# cryobondr-qbit2-aqc.net
KiCad netlist of a schematic drawn in EAGLE
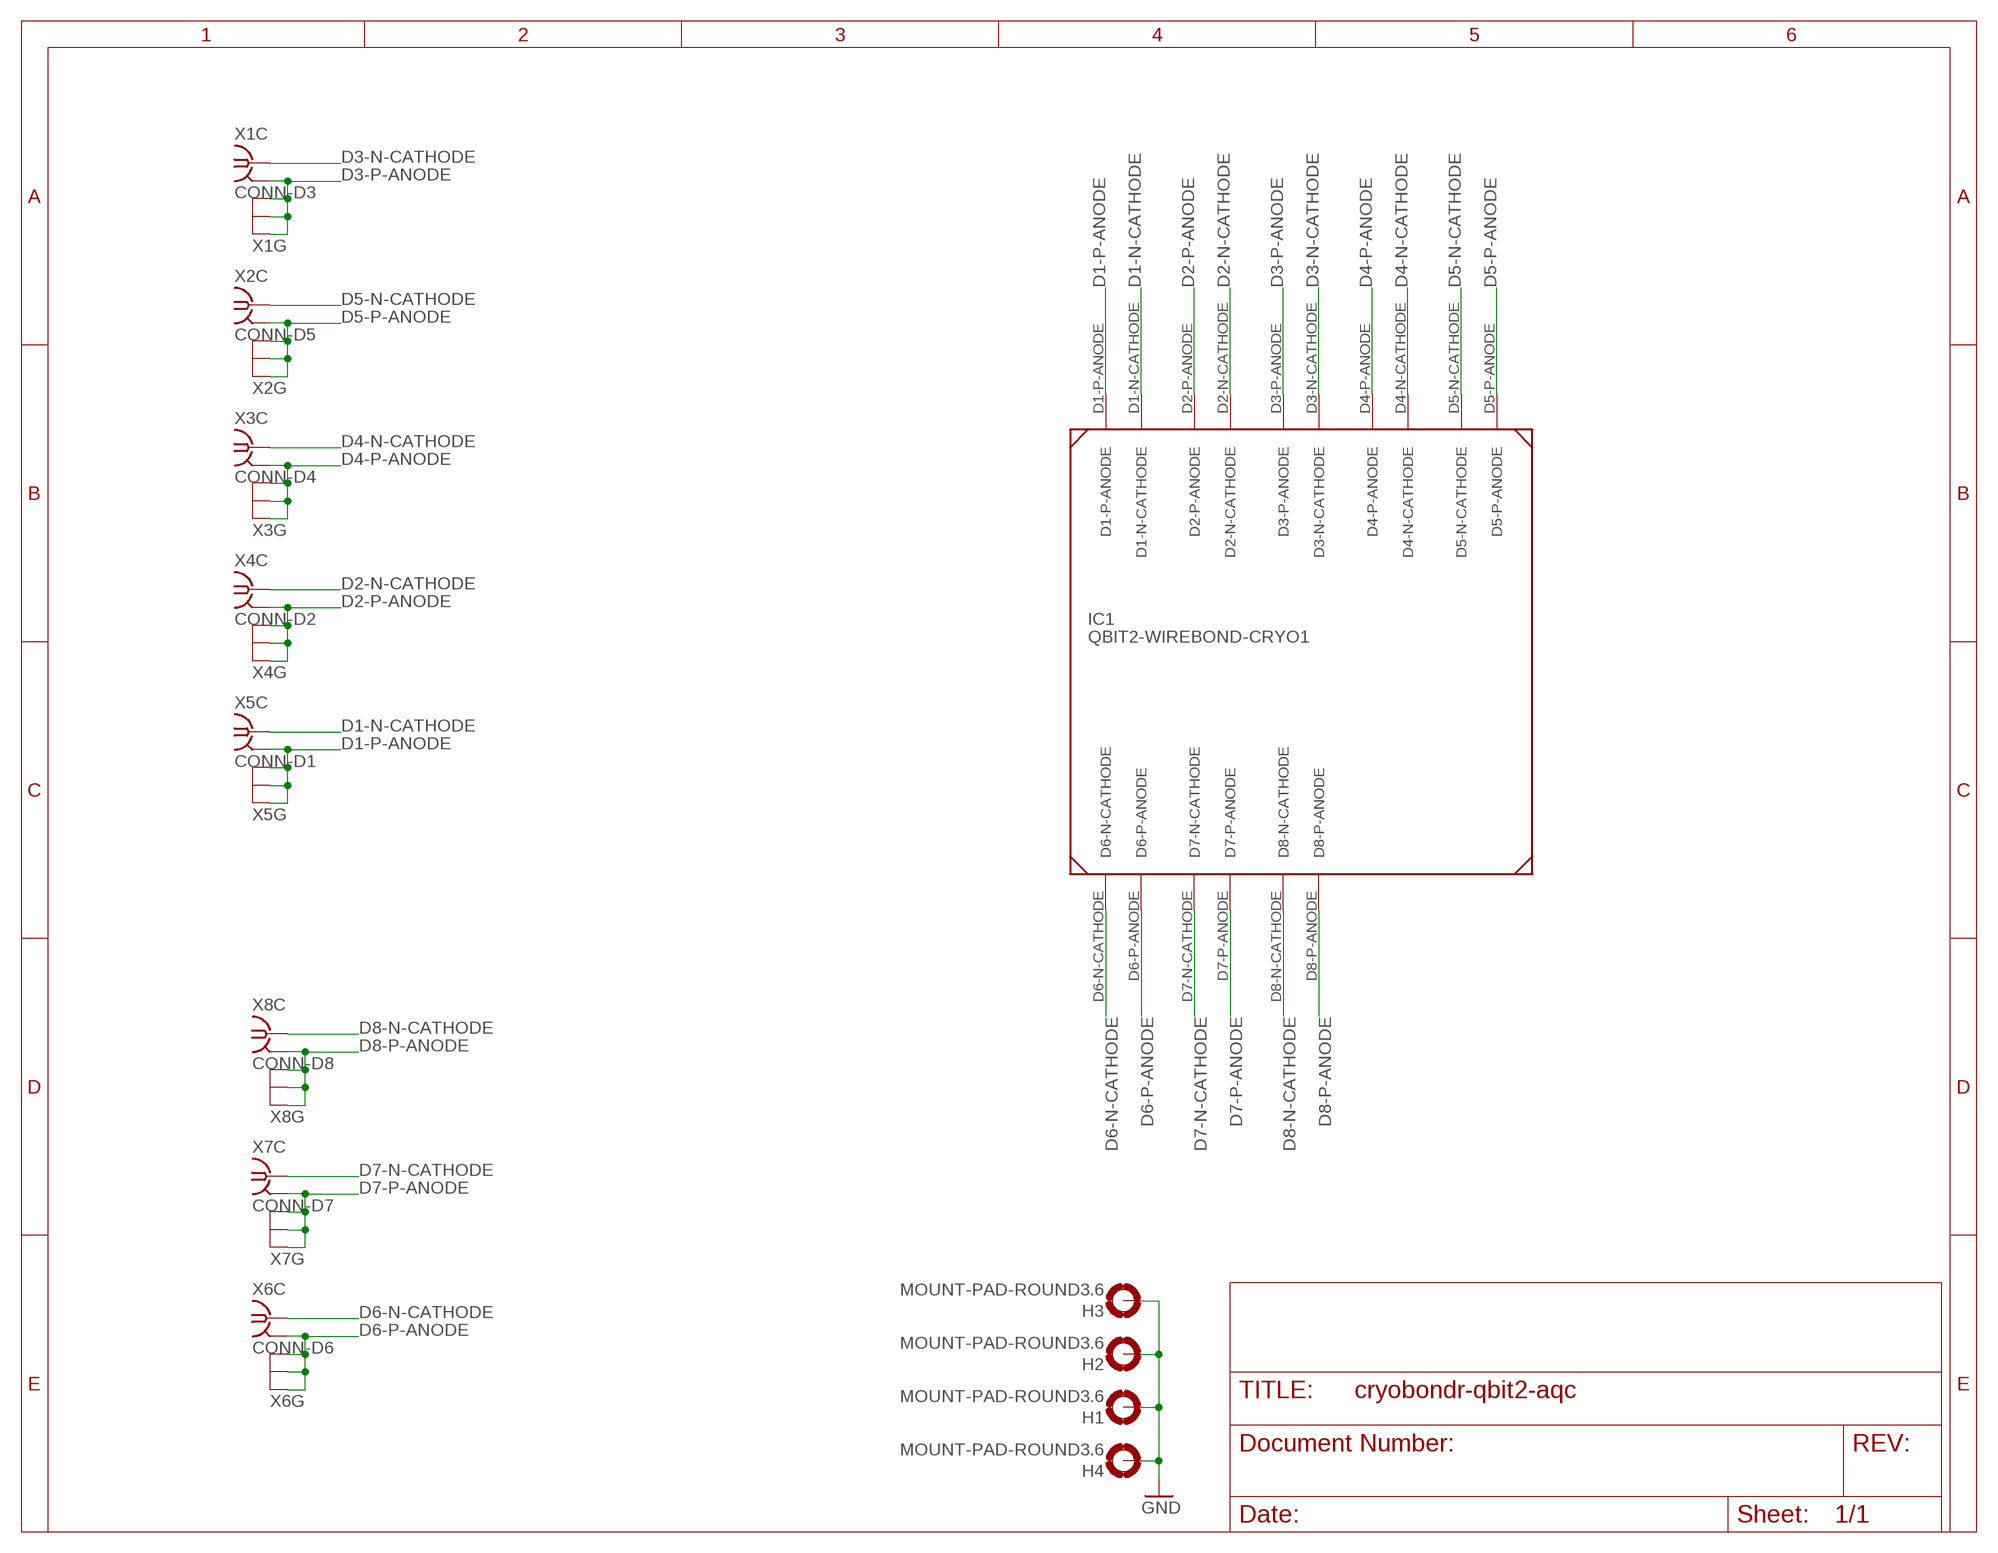
[diagram p0: schematic, sheet 1]

(export (version "E")
  (design (tool "Eeschema 10.0.6"))
  (components
    (comp (ref "H1")
      (value "MOUNT-PAD-ROUND3.6")
      (footprint "eagle-import:3,6-PAD")
      (libsource (lib "eagle-import") (part "MOUNT-PAD-ROUND3.6"))
    )
    (comp (ref "H2")
      (value "MOUNT-PAD-ROUND3.6")
      (footprint "eagle-import:3,6-PAD")
      (libsource (lib "eagle-import") (part "MOUNT-PAD-ROUND3.6"))
    )
    (comp (ref "H3")
      (value "MOUNT-PAD-ROUND3.6")
      (footprint "eagle-import:3,6-PAD")
      (libsource (lib "eagle-import") (part "MOUNT-PAD-ROUND3.6"))
    )
    (comp (ref "H4")
      (value "MOUNT-PAD-ROUND3.6")
      (footprint "eagle-import:3,6-PAD")
      (libsource (lib "eagle-import") (part "MOUNT-PAD-ROUND3.6"))
    )
    (comp (ref "IC1")
      (value "QBIT2-WIREBOND-CRYO1")
      (footprint "eagle-import:QBIT2-WIREBOND-CRYO1")
      (libsource (lib "eagle-import") (part "QBIT2-WIREBOND-CRYO1"))
    )
    (comp (ref "X1")
      (value "CONN-D3")
      (footprint "eagle-import:MMCX-SMT")
      (libsource (lib "eagle-import") (part "MMCX"))
    )
    (comp (ref "X2")
      (value "CONN-D5")
      (footprint "eagle-import:MMCX-SMT")
      (libsource (lib "eagle-import") (part "MMCX"))
    )
    (comp (ref "X3")
      (value "CONN-D4")
      (footprint "eagle-import:MMCX-SMT")
      (libsource (lib "eagle-import") (part "MMCX"))
    )
    (comp (ref "X4")
      (value "CONN-D2")
      (footprint "eagle-import:MMCX-SMT")
      (libsource (lib "eagle-import") (part "MMCX"))
    )
    (comp (ref "X5")
      (value "CONN-D1")
      (footprint "eagle-import:MMCX-SMT")
      (libsource (lib "eagle-import") (part "MMCX"))
    )
    (comp (ref "X6")
      (value "CONN-D6")
      (footprint "eagle-import:MMCX-SMT")
      (libsource (lib "eagle-import") (part "MMCX"))
    )
    (comp (ref "X7")
      (value "CONN-D7")
      (footprint "eagle-import:MMCX-SMT")
      (libsource (lib "eagle-import") (part "MMCX"))
    )
    (comp (ref "X8")
      (value "CONN-D8")
      (footprint "eagle-import:MMCX-SMT")
      (libsource (lib "eagle-import") (part "MMCX"))
    )
  )
  (nets
    (net (code "1") (name "/D1-N-CATHODE") (class "Default")
      (node (ref "IC1") (pin "D1-N-CATHODE") (pinfunction "D1-N-CATHODE_D1-N-CATHODE") (pintype "bidirectional"))
      (node (ref "X5") (pin "S") (pinfunction "1_S") (pintype "passive"))
    )
    (net (code "2") (name "/D1-P-ANODE") (class "Default")
      (node (ref "IC1") (pin "D1-P-ANODE") (pinfunction "D1-P-ANODE_D1-P-ANODE") (pintype "bidirectional"))
      (node (ref "X5") (pin "G1") (pinfunction "GND_G1") (pintype "power_in"))
      (node (ref "X5") (pin "G2") (pinfunction "GND_G2") (pintype "power_in"))
      (node (ref "X5") (pin "G3") (pinfunction "GND_G3") (pintype "power_in"))
      (node (ref "X5") (pin "G4") (pinfunction "GND_G4") (pintype "power_in"))
    )
    (net (code "3") (name "/D2-N-CATHODE") (class "Default")
      (node (ref "IC1") (pin "D2-N-CATHODE") (pinfunction "D2-N-CATHODE_D2-N-CATHODE") (pintype "bidirectional"))
      (node (ref "X4") (pin "S") (pinfunction "1_S") (pintype "passive"))
    )
    (net (code "4") (name "/D2-P-ANODE") (class "Default")
      (node (ref "IC1") (pin "D2-P-ANODE") (pinfunction "D2-P-ANODE_D2-P-ANODE") (pintype "bidirectional"))
      (node (ref "X4") (pin "G1") (pinfunction "GND_G1") (pintype "power_in"))
      (node (ref "X4") (pin "G2") (pinfunction "GND_G2") (pintype "power_in"))
      (node (ref "X4") (pin "G3") (pinfunction "GND_G3") (pintype "power_in"))
      (node (ref "X4") (pin "G4") (pinfunction "GND_G4") (pintype "power_in"))
    )
    (net (code "5") (name "/D3-N-CATHODE") (class "Default")
      (node (ref "IC1") (pin "D3-N-CATHODE") (pinfunction "D3-N-CATHODE_D3-N-CATHODE") (pintype "bidirectional"))
      (node (ref "X1") (pin "S") (pinfunction "1_S") (pintype "passive"))
    )
    (net (code "6") (name "/D3-P-ANODE") (class "Default")
      (node (ref "IC1") (pin "D3-P-ANODE") (pinfunction "D3-P-ANODE_D3-P-ANODE") (pintype "bidirectional"))
      (node (ref "X1") (pin "G1") (pinfunction "GND_G1") (pintype "power_in"))
      (node (ref "X1") (pin "G2") (pinfunction "GND_G2") (pintype "power_in"))
      (node (ref "X1") (pin "G3") (pinfunction "GND_G3") (pintype "power_in"))
      (node (ref "X1") (pin "G4") (pinfunction "GND_G4") (pintype "power_in"))
    )
    (net (code "7") (name "/D4-N-CATHODE") (class "Default")
      (node (ref "IC1") (pin "D4-N-CATHODE") (pinfunction "D4-N-CATHODE_D4-N-CATHODE") (pintype "bidirectional"))
      (node (ref "X3") (pin "S") (pinfunction "1_S") (pintype "passive"))
    )
    (net (code "8") (name "/D4-P-ANODE") (class "Default")
      (node (ref "IC1") (pin "D4-P-ANODE") (pinfunction "D4-P-ANODE_D4-P-ANODE") (pintype "bidirectional"))
      (node (ref "X3") (pin "G1") (pinfunction "GND_G1") (pintype "power_in"))
      (node (ref "X3") (pin "G2") (pinfunction "GND_G2") (pintype "power_in"))
      (node (ref "X3") (pin "G3") (pinfunction "GND_G3") (pintype "power_in"))
      (node (ref "X3") (pin "G4") (pinfunction "GND_G4") (pintype "power_in"))
    )
    (net (code "9") (name "/D5-N-CATHODE") (class "Default")
      (node (ref "IC1") (pin "D5-N-CATHODE") (pinfunction "D5-N-CATHODE_D5-N-CATHODE") (pintype "bidirectional"))
      (node (ref "X2") (pin "S") (pinfunction "1_S") (pintype "passive"))
    )
    (net (code "10") (name "/D5-P-ANODE") (class "Default")
      (node (ref "IC1") (pin "D5-P-ANODE") (pinfunction "D5-P-ANODE_D5-P-ANODE") (pintype "bidirectional"))
      (node (ref "X2") (pin "G1") (pinfunction "GND_G1") (pintype "power_in"))
      (node (ref "X2") (pin "G2") (pinfunction "GND_G2") (pintype "power_in"))
      (node (ref "X2") (pin "G3") (pinfunction "GND_G3") (pintype "power_in"))
      (node (ref "X2") (pin "G4") (pinfunction "GND_G4") (pintype "power_in"))
    )
    (net (code "11") (name "/D6-N-CATHODE") (class "Default")
      (node (ref "IC1") (pin "D6-N-CATHODE") (pinfunction "D6-N-CATHODE_D6-N-CATHODE") (pintype "bidirectional"))
      (node (ref "X6") (pin "S") (pinfunction "1_S") (pintype "passive"))
    )
    (net (code "12") (name "/D6-P-ANODE") (class "Default")
      (node (ref "IC1") (pin "D6-P-ANODE") (pinfunction "D6-P-ANODE_D6-P-ANODE") (pintype "bidirectional"))
      (node (ref "X6") (pin "G1") (pinfunction "GND_G1") (pintype "power_in"))
      (node (ref "X6") (pin "G2") (pinfunction "GND_G2") (pintype "power_in"))
      (node (ref "X6") (pin "G3") (pinfunction "GND_G3") (pintype "power_in"))
      (node (ref "X6") (pin "G4") (pinfunction "GND_G4") (pintype "power_in"))
    )
    (net (code "13") (name "/D7-N-CATHODE") (class "Default")
      (node (ref "IC1") (pin "D7-N-CATHODE") (pinfunction "D7-N-CATHODE_D7-N-CATHODE") (pintype "bidirectional"))
      (node (ref "X7") (pin "S") (pinfunction "1_S") (pintype "passive"))
    )
    (net (code "14") (name "/D7-P-ANODE") (class "Default")
      (node (ref "IC1") (pin "D7-P-ANODE") (pinfunction "D7-P-ANODE_D7-P-ANODE") (pintype "bidirectional"))
      (node (ref "X7") (pin "G1") (pinfunction "GND_G1") (pintype "power_in"))
      (node (ref "X7") (pin "G2") (pinfunction "GND_G2") (pintype "power_in"))
      (node (ref "X7") (pin "G3") (pinfunction "GND_G3") (pintype "power_in"))
      (node (ref "X7") (pin "G4") (pinfunction "GND_G4") (pintype "power_in"))
    )
    (net (code "15") (name "/D8-N-CATHODE") (class "Default")
      (node (ref "IC1") (pin "D8-N-CATHODE") (pinfunction "D8-N-CATHODE_D8-N-CATHODE") (pintype "bidirectional"))
      (node (ref "X8") (pin "S") (pinfunction "1_S") (pintype "passive"))
    )
    (net (code "16") (name "/D8-P-ANODE") (class "Default")
      (node (ref "IC1") (pin "D8-P-ANODE") (pinfunction "D8-P-ANODE_D8-P-ANODE") (pintype "bidirectional"))
      (node (ref "X8") (pin "G1") (pinfunction "GND_G1") (pintype "power_in"))
      (node (ref "X8") (pin "G2") (pinfunction "GND_G2") (pintype "power_in"))
      (node (ref "X8") (pin "G3") (pinfunction "GND_G3") (pintype "power_in"))
      (node (ref "X8") (pin "G4") (pinfunction "GND_G4") (pintype "power_in"))
    )
    (net (code "17") (name "GND") (class "Default")
      (node (ref "H1") (pin "B3,6") (pinfunction "MOUNT_B3,6") (pintype "passive"))
      (node (ref "H2") (pin "B3,6") (pinfunction "MOUNT_B3,6") (pintype "passive"))
      (node (ref "H3") (pin "B3,6") (pinfunction "MOUNT_B3,6") (pintype "passive"))
      (node (ref "H4") (pin "B3,6") (pinfunction "MOUNT_B3,6") (pintype "passive"))
    )
  )
)
